# Singularitron_IR_Thermometer_Module_v1.net
KiCad netlist of a schematic drawn in EAGLE
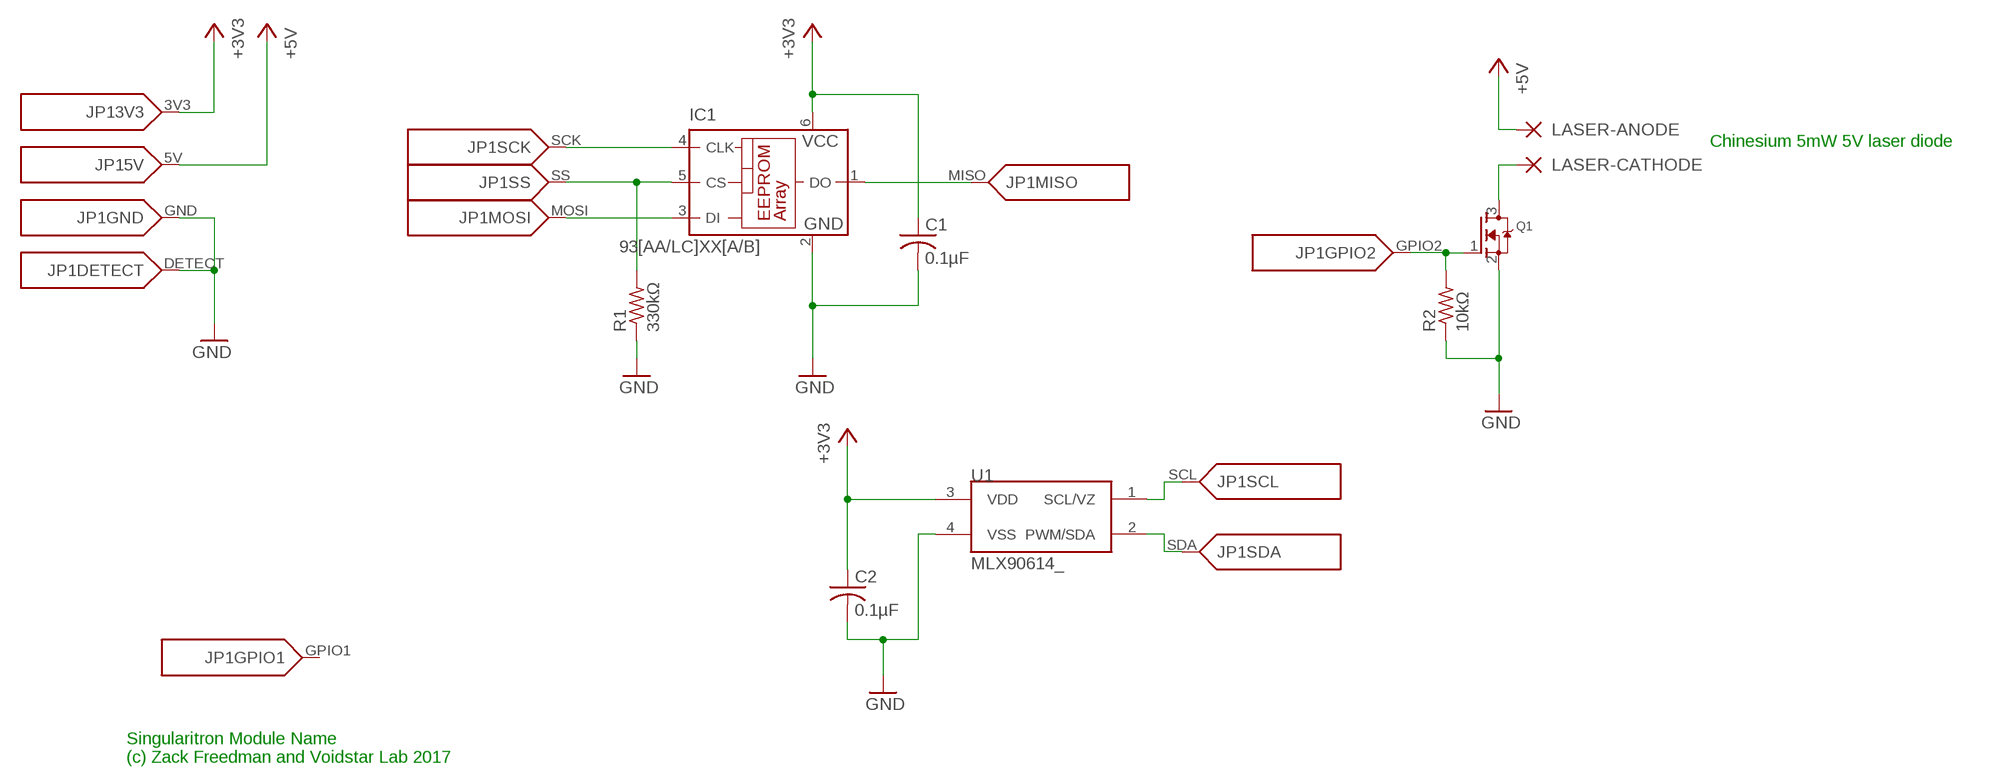
[diagram p0: schematic, sheet 1]

(export (version "E")
  (design (tool "Eeschema 10.0.6"))
  (components
    (comp (ref "C1")
      (value "0.1µF")
      (footprint "eagle-import:C0603")
      (libsource (lib "eagle-import") (part "C-USC0603"))
    )
    (comp (ref "C2")
      (value "0.1µF")
      (footprint "eagle-import:C0603")
      (libsource (lib "eagle-import") (part "C-USC0603"))
    )
    (comp (ref "IC1")
      (value "93[AA/LC]XX[A/B]")
      (footprint "eagle-import:SOT23-6")
      (fields (field (name "MPN") "93AA76AT-I/OT"))
      (libsource (lib "eagle-import") (part "9376?AAA"))
    )
    (comp (ref "JP1")
      (value "SINGULARITRON_CART_BASE")
      (footprint "eagle-import:SINGULARITRON_CART_BASE")
      (libsource (lib "eagle-import") (part "SINGULARITRON_CART_BASE"))
    )
    (comp (ref "LASER-ANODE")
      (value "1,6/0,9")
      (footprint "eagle-import:1,6_0,9")
      (libsource (lib "eagle-import") (part "1,6/0,9"))
    )
    (comp (ref "LASER-CATHODE")
      (value "1,6/0,9")
      (footprint "eagle-import:1,6_0,9")
      (libsource (lib "eagle-import") (part "1,6/0,9"))
    )
    (comp (ref "Q1")
      (value "MOSFET-NREFLOW")
      (footprint "eagle-import:SOT23")
      (libsource (lib "eagle-import") (part "MOSFET-NREFLOW"))
    )
    (comp (ref "R1")
      (value "330kΩ")
      (footprint "eagle-import:R0603")
      (libsource (lib "eagle-import") (part "R-US_R0603"))
    )
    (comp (ref "R2")
      (value "10kΩ")
      (footprint "eagle-import:R0603")
      (libsource (lib "eagle-import") (part "R-US_R0603"))
    )
    (comp (ref "U1")
      (value "MLX90614_")
      (footprint "eagle-import:TO-39")
      (libsource (lib "eagle-import") (part "MLX90614_"))
    )
  )
  (nets
    (net (code "1") (name "+3V3") (class "Default")
      (node (ref "C1") (pin "1") (pinfunction "1_1") (pintype "passive"))
      (node (ref "C2") (pin "1") (pinfunction "1_1") (pintype "passive"))
      (node (ref "IC1") (pin "6") (pinfunction "VCC_6") (pintype "power_in"))
      (node (ref "JP1") (pin "3V3") (pinfunction "P$1_3V3") (pintype "bidirectional"))
      (node (ref "U1") (pin "3") (pinfunction "VDD_3") (pintype "bidirectional"))
    )
    (net (code "2") (name "+5V") (class "Default")
      (node (ref "JP1") (pin "5V") (pinfunction "P$1_5V") (pintype "bidirectional"))
      (node (ref "LASER-ANODE") (pin "1") (pinfunction "P_1") (pintype "passive"))
    )
    (net (code "3") (name "GND") (class "Default")
      (node (ref "C1") (pin "2") (pinfunction "2_2") (pintype "passive"))
      (node (ref "C2") (pin "2") (pinfunction "2_2") (pintype "passive"))
      (node (ref "IC1") (pin "2") (pinfunction "GND_2") (pintype "power_in"))
      (node (ref "JP1") (pin "DETECT") (pinfunction "P$1_DETECT") (pintype "bidirectional"))
      (node (ref "JP1") (pin "GND") (pinfunction "P$1_GND") (pintype "bidirectional"))
      (node (ref "Q1") (pin "2") (pinfunction "S_2") (pintype "bidirectional"))
      (node (ref "R1") (pin "1") (pinfunction "1_1") (pintype "passive"))
      (node (ref "R2") (pin "1") (pinfunction "1_1") (pintype "passive"))
      (node (ref "U1") (pin "4") (pinfunction "VSS_4") (pintype "bidirectional"))
    )
    (net (code "4") (name "Net-(IC1-CLK)") (class "Default")
      (node (ref "IC1") (pin "4") (pinfunction "CLK_4") (pintype "input"))
      (node (ref "JP1") (pin "SCK") (pinfunction "P$1_SCK") (pintype "bidirectional"))
    )
    (net (code "5") (name "Net-(IC1-CS)") (class "Default")
      (node (ref "IC1") (pin "5") (pinfunction "CS_5") (pintype "input"))
      (node (ref "JP1") (pin "SS") (pinfunction "P$1_SS") (pintype "bidirectional"))
      (node (ref "R1") (pin "2") (pinfunction "2_2") (pintype "passive"))
    )
    (net (code "6") (name "Net-(IC1-DI)") (class "Default")
      (node (ref "IC1") (pin "3") (pinfunction "DI_3") (pintype "input"))
      (node (ref "JP1") (pin "MOSI") (pinfunction "P$1_MOSI") (pintype "bidirectional"))
    )
    (net (code "7") (name "Net-(IC1-DO)") (class "Default")
      (node (ref "IC1") (pin "1") (pinfunction "DO_1") (pintype "tri_state"))
      (node (ref "JP1") (pin "MISO") (pinfunction "P$1_MISO") (pintype "bidirectional"))
    )
    (net (code "8") (name "Net-(JP1F-P$1)") (class "Default")
      (node (ref "JP1") (pin "GPIO2") (pinfunction "P$1_GPIO2") (pintype "bidirectional"))
      (node (ref "Q1") (pin "1") (pinfunction "G_1") (pintype "bidirectional"))
      (node (ref "R2") (pin "2") (pinfunction "2_2") (pintype "passive"))
    )
    (net (code "9") (name "Net-(JP1J-P$1)") (class "Default")
      (node (ref "JP1") (pin "SCL") (pinfunction "P$1_SCL") (pintype "bidirectional"))
      (node (ref "U1") (pin "1") (pinfunction "SCL/VZ_1") (pintype "bidirectional"))
    )
    (net (code "10") (name "Net-(JP1K-P$1)") (class "Default")
      (node (ref "JP1") (pin "SDA") (pinfunction "P$1_SDA") (pintype "bidirectional"))
      (node (ref "U1") (pin "2") (pinfunction "PWM/SDA_2") (pintype "bidirectional"))
    )
    (net (code "11") (name "Net-(LASER-CATHODE-P)") (class "Default")
      (node (ref "LASER-CATHODE") (pin "1") (pinfunction "P_1") (pintype "passive"))
      (node (ref "Q1") (pin "3") (pinfunction "D_3") (pintype "bidirectional"))
    )
    (net (code "12") (name "unconnected-(JP1E-P$1-PadGPIO1)") (class "Default")
      (node (ref "JP1") (pin "GPIO1") (pinfunction "P$1_GPIO1") (pintype "bidirectional"))
    )
  )
)
